# stepper_cfg.net
KiCad netlist of a schematic drawn in Altium Designer
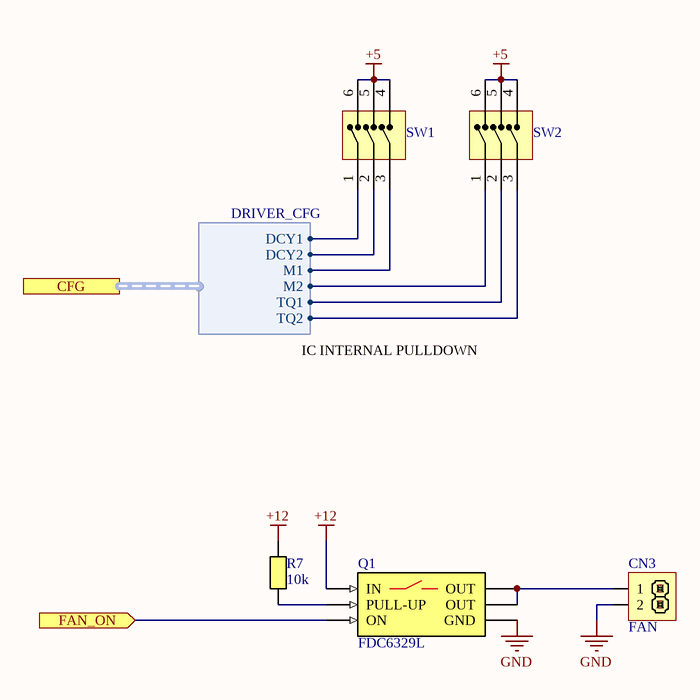
[diagram p0: stepper_cfg.SchDoc]

(export (version "E")
  (design (tool "Eeschema 10.0.6"))
  (components
    (comp (ref "CN3")
      (value "FAN")
      (footprint "XH2.54 2P")
      (libsource (lib "Connectors") (part "PIN HEADER 2.54 1x2"))
    )
    (comp (ref "Q1")
      (value "FDC6329L")
      (footprint "SuperSOT-6")
      (description "2A Integrated Load Switch SuperSOT-6 SMD")
      (libsource (lib "Switches") (part "FDC6329L"))
    )
    (comp (ref "R7")
      (value "10k")
      (footprint "RESC0603(1608)_N")
      (description "Resistor Medium Density")
      (libsource (lib "Discrete") (part "Resistor M"))
    )
    (comp (ref "SW1")
      (value "DIP Switch 6P")
      (footprint "DIP Switch 6P")
      (libsource (lib "Switches") (part "DIP Switch 6P"))
    )
    (comp (ref "SW2")
      (value "DIP Switch 6P")
      (footprint "DIP Switch 6P")
      (libsource (lib "Switches") (part "DIP Switch 6P"))
    )
  )
  (nets
    (net (code "2") (name "+5") (class "Default")
      (node (ref "SW1") (pin "4") (pintype "passive"))
      (node (ref "SW1") (pin "5") (pintype "passive"))
      (node (ref "SW1") (pin "6") (pintype "passive"))
      (node (ref "SW2") (pin "4") (pintype "passive"))
      (node (ref "SW2") (pin "5") (pintype "passive"))
      (node (ref "SW2") (pin "6") (pintype "passive"))
    )
    (net (code "3") (name "+12") (class "Default")
      (node (ref "Q1") (pin "4") (pinfunction "IN_4") (pintype "input"))
      (node (ref "R7") (pin "2") (pinfunction "2_2") (pintype "passive"))
    )
    (net (code "4") (name "/DCY1") (class "Default") (node (ref "SW1") (pin "1") (pintype "passive")))
    (net (code "5") (name "/DCY2") (class "Default") (node (ref "SW1") (pin "2") (pintype "passive")))
    (net (code "6") (name "/FAN_ON") (class "Default")
      (node (ref "Q1") (pin "5") (pinfunction "ON_5") (pintype "input"))
    )
    (net (code "7") (name "/M1") (class "Default") (node (ref "SW1") (pin "3") (pintype "passive")))
    (net (code "8") (name "/M2") (class "Default") (node (ref "SW2") (pin "1") (pintype "passive")))
    (net (code "9") (name "/TQ1") (class "Default") (node (ref "SW2") (pin "2") (pintype "passive")))
    (net (code "10") (name "/TQ2") (class "Default") (node (ref "SW2") (pin "3") (pintype "passive")))
    (net (code "12") (name "GND") (class "Default")
      (node (ref "CN3") (pin "2") (pinfunction "2_2") (pintype "passive"))
      (node (ref "Q1") (pin "1") (pinfunction "GND_1") (pintype "power_in"))
    )
    (net (code "13") (name "Net-(CN3-Pad1)") (class "Default")
      (node (ref "CN3") (pin "1") (pinfunction "1_1") (pintype "passive"))
      (node (ref "Q1") (pin "2") (pinfunction "OUT_2") (pintype "power_in"))
      (node (ref "Q1") (pin "3") (pinfunction "OUT_3") (pintype "power_in"))
    )
    (net (code "14") (name "Net-(Q1-PULL-UP)") (class "Default")
      (node (ref "Q1") (pin "6") (pinfunction "PULL-UP_6") (pintype "input"))
      (node (ref "R7") (pin "1") (pinfunction "1_1") (pintype "passive"))
    )
  )
)
